# KC_BaseBoardSch.net
KiCad netlist of a schematic drawn in Altium Designer
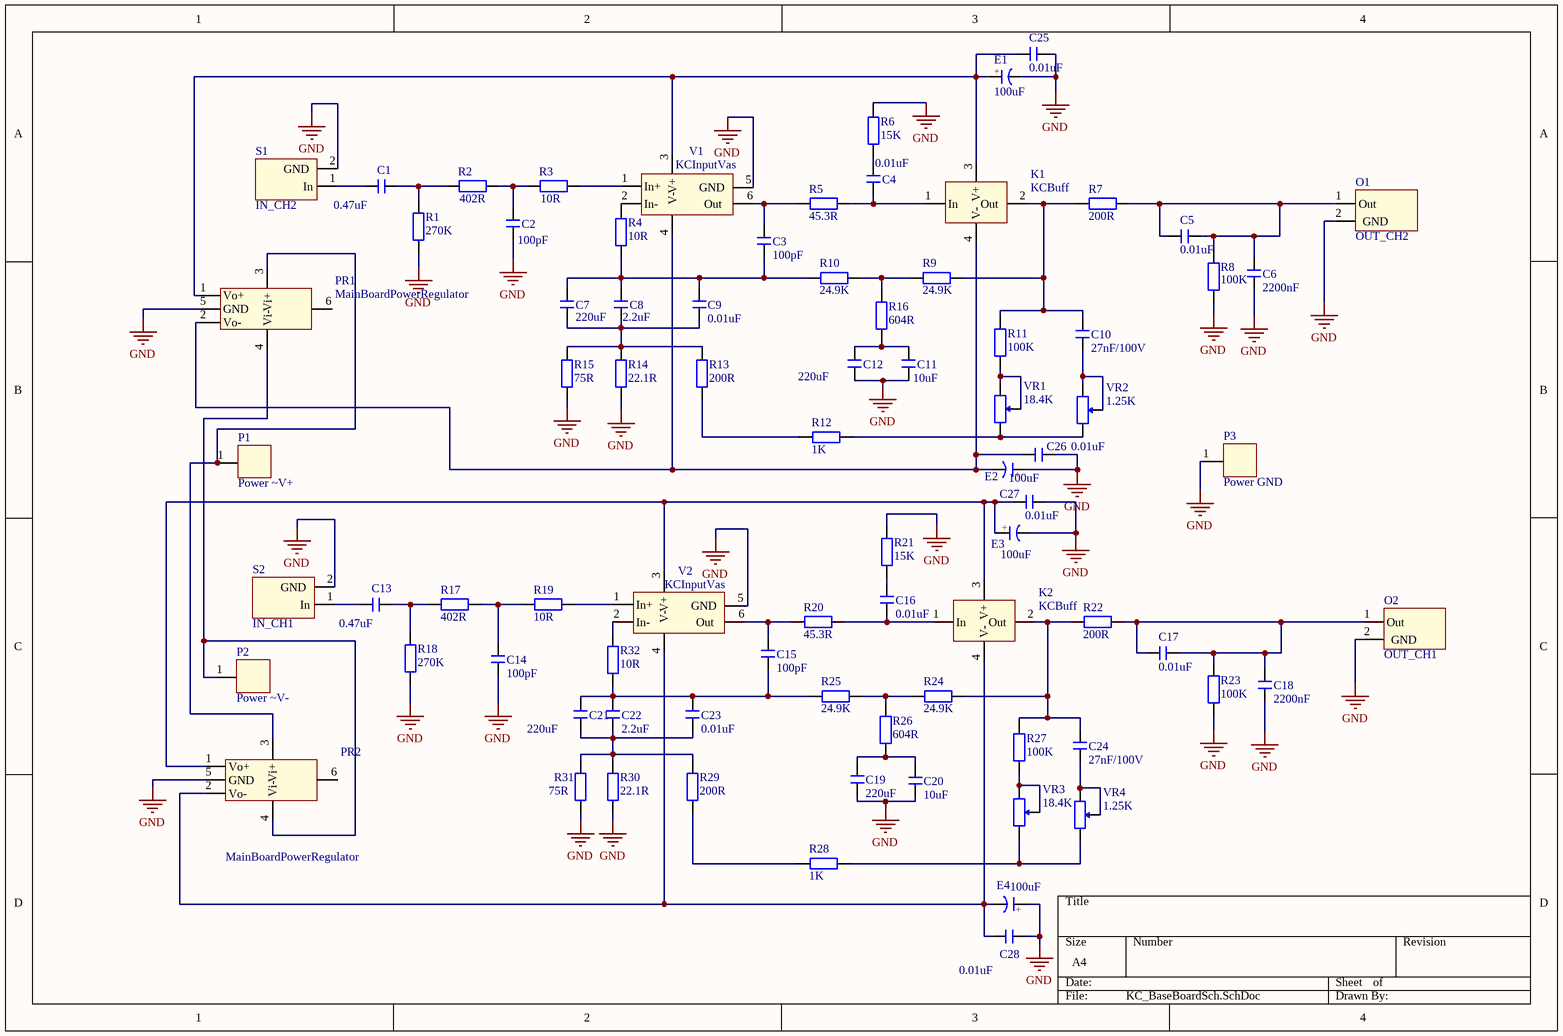
[diagram p0: KC_BaseBoardSch.SchDoc]

(export (version "E")
  (design (tool "Eeschema 10.0.6"))
  (components
    (comp (ref "C1")
      (value "0.47uF")
      (footprint "CBB 50*30*30")
      (description "CBB电容")
      (fields (field (name "版权归属") "源创客"))
      (libsource (lib "电阻-电容-电感") (part "C-CBB"))
    )
    (comp (ref "C2")
      (value "100pF")
      (footprint "CBB 6.3*6.3*5")
      (description "CBB电容")
      (fields (field (name "版权归属") "源创客"))
      (libsource (lib "电阻-电容-电感") (part "C-CBB"))
    )
    (comp (ref "C3")
      (value "100pF")
      (footprint "CBB 6.3*6.3*5")
      (description "CBB电容")
      (fields (field (name "版权归属") "源创客"))
      (libsource (lib "电阻-电容-电感") (part "C-CBB"))
    )
    (comp (ref "C4")
      (value "0.01uF")
      (footprint "CBB 6.3*6.3*5")
      (description "CBB电容")
      (fields (field (name "版权归属") "源创客"))
      (libsource (lib "电阻-电容-电感") (part "C-CBB"))
    )
    (comp (ref "C5")
      (value "0.01uF")
      (footprint "CBB 6.3*6.3*5")
      (description "CBB电容")
      (fields (field (name "版权归属") "源创客"))
      (libsource (lib "电阻-电容-电感") (part "C-CBB"))
    )
    (comp (ref "C6")
      (value "2200nF")
      (footprint "CBB 6.3*6.3*5")
      (description "CBB电容")
      (fields (field (name "版权归属") "源创客"))
      (libsource (lib "电阻-电容-电感") (part "C-CBB"))
    )
    (comp (ref "C7")
      (value "220uF")
      (footprint "CBB 6.3*6.3*5")
      (description "CBB电容")
      (fields (field (name "版权归属") "源创客"))
      (libsource (lib "电阻-电容-电感") (part "C-CBB"))
    )
    (comp (ref "C8")
      (value "2.2uF")
      (footprint "CBB 6.3*6.3*5")
      (description "CBB电容")
      (fields (field (name "版权归属") "源创客"))
      (libsource (lib "电阻-电容-电感") (part "C-CBB"))
    )
    (comp (ref "C9")
      (value "0.01uF")
      (footprint "CBB 6.3*6.3*5")
      (description "CBB电容")
      (fields (field (name "版权归属") "源创客"))
      (libsource (lib "电阻-电容-电感") (part "C-CBB"))
    )
    (comp (ref "C10")
      (value "27nF/100V")
      (footprint "CBB 15*18*11")
      (description "CBB电容")
      (fields (field (name "版权归属") "源创客"))
      (libsource (lib "电阻-电容-电感") (part "C-CBB"))
    )
    (comp (ref "C11")
      (value "10uF")
      (footprint "CBB 6.3*6.3*5")
      (description "CBB电容")
      (fields (field (name "版权归属") "源创客"))
      (libsource (lib "电阻-电容-电感") (part "C-CBB"))
    )
    (comp (ref "C12")
      (value "220uF")
      (footprint "CBB 6.3*6.3*5")
      (description "CBB电容")
      (fields (field (name "版权归属") "源创客"))
      (libsource (lib "电阻-电容-电感") (part "C-CBB"))
    )
    (comp (ref "C13")
      (value "0.47uF")
      (footprint "CBB 50*30*30")
      (description "CBB电容")
      (fields (field (name "版权归属") "源创客"))
      (libsource (lib "电阻-电容-电感") (part "C-CBB"))
    )
    (comp (ref "C14")
      (value "100pF")
      (footprint "CBB 6.3*6.3*5")
      (description "CBB电容")
      (fields (field (name "版权归属") "源创客"))
      (libsource (lib "电阻-电容-电感") (part "C-CBB"))
    )
    (comp (ref "C15")
      (value "100pF")
      (footprint "CBB 6.3*6.3*5")
      (description "CBB电容")
      (fields (field (name "版权归属") "源创客"))
      (libsource (lib "电阻-电容-电感") (part "C-CBB"))
    )
    (comp (ref "C16")
      (value "0.01uF")
      (footprint "CBB 6.3*6.3*5")
      (description "CBB电容")
      (fields (field (name "版权归属") "源创客"))
      (libsource (lib "电阻-电容-电感") (part "C-CBB"))
    )
    (comp (ref "C17")
      (value "0.01uF")
      (footprint "CBB 6.3*6.3*5")
      (description "CBB电容")
      (fields (field (name "版权归属") "源创客"))
      (libsource (lib "电阻-电容-电感") (part "C-CBB"))
    )
    (comp (ref "C18")
      (value "2200nF")
      (footprint "CBB 6.3*6.3*5")
      (description "CBB电容")
      (fields (field (name "版权归属") "源创客"))
      (libsource (lib "电阻-电容-电感") (part "C-CBB"))
    )
    (comp (ref "C19")
      (value "220uF")
      (footprint "CBB 6.3*6.3*5")
      (description "CBB电容")
      (fields (field (name "版权归属") "源创客"))
      (libsource (lib "电阻-电容-电感") (part "C-CBB"))
    )
    (comp (ref "C20")
      (value "10uF")
      (footprint "CBB 6.3*6.3*5")
      (description "CBB电容")
      (fields (field (name "版权归属") "源创客"))
      (libsource (lib "电阻-电容-电感") (part "C-CBB"))
    )
    (comp (ref "C21")
      (value "220uF")
      (footprint "CBB 6.3*6.3*5")
      (description "CBB电容")
      (fields (field (name "版权归属") "源创客"))
      (libsource (lib "电阻-电容-电感") (part "C-CBB"))
    )
    (comp (ref "C22")
      (value "2.2uF")
      (footprint "CBB 6.3*6.3*5")
      (description "CBB电容")
      (fields (field (name "版权归属") "源创客"))
      (libsource (lib "电阻-电容-电感") (part "C-CBB"))
    )
    (comp (ref "C23")
      (value "0.01uF")
      (footprint "CBB 6.3*6.3*5")
      (description "CBB电容")
      (fields (field (name "版权归属") "源创客"))
      (libsource (lib "电阻-电容-电感") (part "C-CBB"))
    )
    (comp (ref "C24")
      (value "27nF/100V")
      (footprint "CBB 15*18*11")
      (description "CBB电容")
      (fields (field (name "版权归属") "源创客"))
      (libsource (lib "电阻-电容-电感") (part "C-CBB"))
    )
    (comp (ref "C25")
      (value "0.01uF")
      (footprint "CBB 6.3*6.3*5")
      (description "CBB电容")
      (fields (field (name "版权归属") "源创客"))
      (libsource (lib "电阻-电容-电感") (part "C-CBB"))
    )
    (comp (ref "C26")
      (value "0.01uF")
      (footprint "CBB 6.3*6.3*5")
      (description "CBB电容")
      (fields (field (name "版权归属") "源创客"))
      (libsource (lib "电阻-电容-电感") (part "C-CBB"))
    )
    (comp (ref "C27")
      (value "0.01uF")
      (footprint "CBB 6.3*6.3*5")
      (description "CBB电容")
      (fields (field (name "版权归属") "源创客"))
      (libsource (lib "电阻-电容-电感") (part "C-CBB"))
    )
    (comp (ref "C28")
      (value "0.01uF")
      (footprint "CBB 6.3*6.3*5")
      (description "CBB电容")
      (fields (field (name "版权归属") "源创客"))
      (libsource (lib "电阻-电容-电感") (part "C-CBB"))
    )
    (comp (ref "E1")
      (value "100uF")
      (footprint "CAP 5.0*10*20")
      (description "直插电解电容")
      (fields (field (name "版权归属") "源创客"))
      (libsource (lib "电阻-电容-电感") (part "C-CAP"))
    )
    (comp (ref "E2")
      (value "100uF")
      (footprint "CAP 5.0*10*20")
      (description "直插电解电容")
      (fields (field (name "版权归属") "源创客"))
      (libsource (lib "电阻-电容-电感") (part "C-CAP"))
    )
    (comp (ref "E3")
      (value "100uF")
      (footprint "CAP 5.0*10*20")
      (description "直插电解电容")
      (fields (field (name "版权归属") "源创客"))
      (libsource (lib "电阻-电容-电感") (part "C-CAP"))
    )
    (comp (ref "E4")
      (value "100uF")
      (footprint "CAP 5.0*10*20")
      (description "直插电解电容")
      (fields (field (name "版权归属") "源创客"))
      (libsource (lib "电阻-电容-电感") (part "C-CAP"))
    )
    (comp (ref "K1")
      (value "KCBuff")
      (footprint "KCBuff")
      (description "King Cello Buffer Stage")
      (libsource (lib "KC_amp") (part "KCBuff"))
    )
    (comp (ref "K2")
      (value "KCBuff")
      (footprint "KCBuff")
      (description "King Cello Buffer Stage")
      (libsource (lib "KC_amp") (part "KCBuff"))
    )
    (comp (ref "O1")
      (value "OUT_CH2")
      (footprint "Signal_Terminal")
      (description "Signal Out")
      (libsource (lib "KC_amp") (part "Signal_Out"))
    )
    (comp (ref "O2")
      (value "OUT_CH1")
      (footprint "Signal_Terminal")
      (description "Signal Out")
      (libsource (lib "KC_amp") (part "Signal_Out"))
    )
    (comp (ref "P1")
      (value "Power ~V+")
      (footprint "SinglePin")
      (description "Power Pin")
      (libsource (lib "KC_amp") (part "PowerPin"))
    )
    (comp (ref "P2")
      (value "Power ~V-")
      (footprint "SinglePin")
      (description "Power Pin")
      (libsource (lib "KC_amp") (part "PowerPin"))
    )
    (comp (ref "P3") (value "Power GND") (footprint "SinglePin") (libsource (lib "KC_amp") (part "PowerPin")))
    (comp (ref "PR1")
      (value "MainBoardPowerRegulator")
      (footprint "KC_MBPowerReg")
      (description "King Cello Main Board Power Regulator")
      (libsource (lib "KC_amp") (part "MainBoardPowerRegulator"))
    )
    (comp (ref "PR2")
      (value "MainBoardPowerRegulator")
      (footprint "KC_MBPowerReg")
      (description "King Cello Main Board Power Regulator")
      (libsource (lib "KC_amp") (part "MainBoardPowerRegulator"))
    )
    (comp (ref "R1")
      (value "270K")
      (footprint "RS 1/2W")
      (description "直插色环电阻")
      (fields (field (name "版权归属") "源创客"))
      (libsource (lib "电阻-电容-电感") (part "R-CRR"))
    )
    (comp (ref "R2")
      (value "402R")
      (footprint "RS 1/2W")
      (description "直插色环电阻")
      (fields (field (name "版权归属") "源创客"))
      (libsource (lib "电阻-电容-电感") (part "R-CRR"))
    )
    (comp (ref "R3")
      (value "10R")
      (footprint "RS 1/2W")
      (description "直插色环电阻")
      (fields (field (name "版权归属") "源创客"))
      (libsource (lib "电阻-电容-电感") (part "R-CRR"))
    )
    (comp (ref "R4")
      (value "10R")
      (footprint "RS 1/2W")
      (description "直插色环电阻")
      (fields (field (name "版权归属") "源创客"))
      (libsource (lib "电阻-电容-电感") (part "R-CRR"))
    )
    (comp (ref "R5")
      (value "45.3R")
      (footprint "RS 1/2W")
      (description "直插色环电阻")
      (fields (field (name "版权归属") "源创客"))
      (libsource (lib "电阻-电容-电感") (part "R-CRR"))
    )
    (comp (ref "R6")
      (value "15K")
      (footprint "RS 1/2W")
      (description "直插色环电阻")
      (fields (field (name "版权归属") "源创客"))
      (libsource (lib "电阻-电容-电感") (part "R-CRR"))
    )
    (comp (ref "R7")
      (value "200R")
      (footprint "RS 1W")
      (description "直插色环电阻")
      (fields (field (name "版权归属") "源创客"))
      (libsource (lib "电阻-电容-电感") (part "R-CRR"))
    )
    (comp (ref "R8")
      (value "100K")
      (footprint "RS 1/2W")
      (description "直插色环电阻")
      (fields (field (name "版权归属") "源创客"))
      (libsource (lib "电阻-电容-电感") (part "R-CRR"))
    )
    (comp (ref "R9")
      (value "24.9K")
      (footprint "RS 1/2W")
      (description "直插色环电阻")
      (fields (field (name "版权归属") "源创客"))
      (libsource (lib "电阻-电容-电感") (part "R-CRR"))
    )
    (comp (ref "R10")
      (value "24.9K")
      (footprint "RS 1/2W")
      (description "直插色环电阻")
      (fields (field (name "版权归属") "源创客"))
      (libsource (lib "电阻-电容-电感") (part "R-CRR"))
    )
    (comp (ref "R11")
      (value "100K")
      (footprint "RS 1/2W")
      (description "直插色环电阻")
      (fields (field (name "版权归属") "源创客"))
      (libsource (lib "电阻-电容-电感") (part "R-CRR"))
    )
    (comp (ref "R12")
      (value "1K")
      (footprint "RS 1/2W")
      (description "直插色环电阻")
      (fields (field (name "版权归属") "源创客"))
      (libsource (lib "电阻-电容-电感") (part "R-CRR"))
    )
    (comp (ref "R13")
      (value "200R")
      (footprint "RS 1/2W")
      (description "直插色环电阻")
      (fields (field (name "版权归属") "源创客"))
      (libsource (lib "电阻-电容-电感") (part "R-CRR"))
    )
    (comp (ref "R14")
      (value "22.1R")
      (footprint "RS 1/2W")
      (description "直插色环电阻")
      (fields (field (name "版权归属") "源创客"))
      (libsource (lib "电阻-电容-电感") (part "R-CRR"))
    )
    (comp (ref "R15")
      (value "75R")
      (footprint "RS 1/2W")
      (description "直插色环电阻")
      (fields (field (name "版权归属") "源创客"))
      (libsource (lib "电阻-电容-电感") (part "R-CRR"))
    )
    (comp (ref "R16")
      (value "604R")
      (footprint "RS 1W")
      (description "直插色环电阻")
      (fields (field (name "版权归属") "源创客"))
      (libsource (lib "电阻-电容-电感") (part "R-CRR"))
    )
    (comp (ref "R17")
      (value "402R")
      (footprint "RS 1/2W")
      (description "直插色环电阻")
      (fields (field (name "版权归属") "源创客"))
      (libsource (lib "电阻-电容-电感") (part "R-CRR"))
    )
    (comp (ref "R18")
      (value "270K")
      (footprint "RS 1/2W")
      (description "直插色环电阻")
      (fields (field (name "版权归属") "源创客"))
      (libsource (lib "电阻-电容-电感") (part "R-CRR"))
    )
    (comp (ref "R19")
      (value "10R")
      (footprint "RS 1/2W")
      (description "直插色环电阻")
      (fields (field (name "版权归属") "源创客"))
      (libsource (lib "电阻-电容-电感") (part "R-CRR"))
    )
    (comp (ref "R20")
      (value "45.3R")
      (footprint "RS 1/2W")
      (description "直插色环电阻")
      (fields (field (name "版权归属") "源创客"))
      (libsource (lib "电阻-电容-电感") (part "R-CRR"))
    )
    (comp (ref "R21")
      (value "15K")
      (footprint "RS 1/2W")
      (description "直插色环电阻")
      (fields (field (name "版权归属") "源创客"))
      (libsource (lib "电阻-电容-电感") (part "R-CRR"))
    )
    (comp (ref "R22")
      (value "200R")
      (footprint "RS 1W")
      (description "直插色环电阻")
      (fields (field (name "版权归属") "源创客"))
      (libsource (lib "电阻-电容-电感") (part "R-CRR"))
    )
    (comp (ref "R23")
      (value "100K")
      (footprint "RS 1/2W")
      (description "直插色环电阻")
      (fields (field (name "版权归属") "源创客"))
      (libsource (lib "电阻-电容-电感") (part "R-CRR"))
    )
    (comp (ref "R24")
      (value "24.9K")
      (footprint "RS 1/2W")
      (description "直插色环电阻")
      (fields (field (name "版权归属") "源创客"))
      (libsource (lib "电阻-电容-电感") (part "R-CRR"))
    )
    (comp (ref "R25")
      (value "24.9K")
      (footprint "RS 1/2W")
      (description "直插色环电阻")
      (fields (field (name "版权归属") "源创客"))
      (libsource (lib "电阻-电容-电感") (part "R-CRR"))
    )
    (comp (ref "R26")
      (value "604R")
      (footprint "RS 1W")
      (description "直插色环电阻")
      (fields (field (name "版权归属") "源创客"))
      (libsource (lib "电阻-电容-电感") (part "R-CRR"))
    )
    (comp (ref "R27")
      (value "100K")
      (footprint "RS 1/2W")
      (description "直插色环电阻")
      (fields (field (name "版权归属") "源创客"))
      (libsource (lib "电阻-电容-电感") (part "R-CRR"))
    )
    (comp (ref "R28")
      (value "1K")
      (footprint "RS 1/2W")
      (description "直插色环电阻")
      (fields (field (name "版权归属") "源创客"))
      (libsource (lib "电阻-电容-电感") (part "R-CRR"))
    )
    (comp (ref "R29")
      (value "200R")
      (footprint "RS 1/2W")
      (description "直插色环电阻")
      (fields (field (name "版权归属") "源创客"))
      (libsource (lib "电阻-电容-电感") (part "R-CRR"))
    )
    (comp (ref "R30")
      (value "22.1R")
      (footprint "RS 1/2W")
      (description "直插色环电阻")
      (fields (field (name "版权归属") "源创客"))
      (libsource (lib "电阻-电容-电感") (part "R-CRR"))
    )
    (comp (ref "R31")
      (value "75R")
      (footprint "RS 1/2W")
      (description "直插色环电阻")
      (fields (field (name "版权归属") "源创客"))
      (libsource (lib "电阻-电容-电感") (part "R-CRR"))
    )
    (comp (ref "R32")
      (value "10R")
      (footprint "RS 1/2W")
      (description "直插色环电阻")
      (fields (field (name "版权归属") "源创客"))
      (libsource (lib "电阻-电容-电感") (part "R-CRR"))
    )
    (comp (ref "S1")
      (value "IN_CH2")
      (footprint "Signal_Terminal")
      (description "Signal In")
      (libsource (lib "KC_amp") (part "Signal_In"))
    )
    (comp (ref "S2")
      (value "IN_CH1")
      (footprint "Signal_Terminal")
      (description "Signal In")
      (libsource (lib "KC_amp") (part "Signal_In"))
    )
    (comp (ref "V1")
      (value "KCInputVas")
      (footprint "KCIn_VAS")
      (description "King Cello Input Stage and VAS")
      (libsource (lib "KC_amp") (part "KCInputVas"))
    )
    (comp (ref "V2")
      (value "KCInputVas")
      (footprint "KCIn_VAS")
      (description "King Cello Input Stage and VAS")
      (libsource (lib "KC_amp") (part "KCInputVas"))
    )
    (comp (ref "VR1")
      (value "18.4K")
      (footprint "RS 1/2W-VR")
      (description "直插可调电阻-顶调")
      (libsource (lib "电阻-电容-电感") (part "VR-W"))
    )
    (comp (ref "VR2")
      (value "1.25K")
      (footprint "RS 1/2W-VR")
      (description "直插可调电阻-顶调")
      (libsource (lib "电阻-电容-电感") (part "VR-W"))
    )
    (comp (ref "VR3")
      (value "18.4K")
      (footprint "RS 1/2W-VR")
      (description "直插可调电阻-顶调")
      (libsource (lib "电阻-电容-电感") (part "VR-W"))
    )
    (comp (ref "VR4")
      (value "1.25K")
      (footprint "RS 1/2W-VR")
      (description "直插可调电阻-顶调")
      (libsource (lib "电阻-电容-电感") (part "VR-W"))
    )
  )
  (nets
    (net (code "1") (name "GND") (class "Default")
      (node (ref "C11") (pin "1") (pinfunction "1_1") (pintype "passive"))
      (node (ref "C12") (pin "1") (pinfunction "1_1") (pintype "passive"))
      (node (ref "C14") (pin "1") (pinfunction "1_1") (pintype "passive"))
      (node (ref "C18") (pin "2") (pinfunction "2_2") (pintype "passive"))
      (node (ref "C19") (pin "2") (pinfunction "2_2") (pintype "passive"))
      (node (ref "C2") (pin "1") (pinfunction "1_1") (pintype "passive"))
      (node (ref "C20") (pin "2") (pinfunction "2_2") (pintype "passive"))
      (node (ref "C25") (pin "2") (pinfunction "2_2") (pintype "passive"))
      (node (ref "C26") (pin "2") (pinfunction "2_2") (pintype "passive"))
      (node (ref "C27") (pin "2") (pinfunction "2_2") (pintype "passive"))
      (node (ref "C28") (pin "2") (pinfunction "2_2") (pintype "passive"))
      (node (ref "C6") (pin "1") (pinfunction "1_1") (pintype "passive"))
      (node (ref "E1") (pin "2") (pinfunction "K_2") (pintype "passive"))
      (node (ref "E2") (pin "1") (pinfunction "A_1") (pintype "passive"))
      (node (ref "E3") (pin "2") (pinfunction "K_2") (pintype "passive"))
      (node (ref "E4") (pin "1") (pinfunction "A_1") (pintype "passive"))
      (node (ref "O1") (pin "2") (pinfunction "GND_2") (pintype "passive"))
      (node (ref "O2") (pin "2") (pinfunction "GND_2") (pintype "passive"))
      (node (ref "P3") (pin "1") (pintype "passive"))
      (node (ref "PR1") (pin "5") (pinfunction "GND_5") (pintype "passive"))
      (node (ref "PR2") (pin "5") (pinfunction "GND_5") (pintype "passive"))
      (node (ref "R1") (pin "1") (pinfunction "1_1") (pintype "passive"))
      (node (ref "R14") (pin "1") (pinfunction "1_1") (pintype "passive"))
      (node (ref "R15") (pin "1") (pinfunction "1_1") (pintype "passive"))
      (node (ref "R18") (pin "1") (pinfunction "1_1") (pintype "passive"))
      (node (ref "R21") (pin "2") (pinfunction "2_2") (pintype "passive"))
      (node (ref "R23") (pin "2") (pinfunction "2_2") (pintype "passive"))
      (node (ref "R30") (pin "1") (pinfunction "1_1") (pintype "passive"))
      (node (ref "R31") (pin "1") (pinfunction "1_1") (pintype "passive"))
      (node (ref "R6") (pin "1") (pinfunction "1_1") (pintype "passive"))
      (node (ref "R8") (pin "1") (pinfunction "1_1") (pintype "passive"))
      (node (ref "S1") (pin "2") (pinfunction "GND_2") (pintype "passive"))
      (node (ref "S2") (pin "2") (pinfunction "GND_2") (pintype "passive"))
      (node (ref "V1") (pin "5") (pinfunction "GND_5") (pintype "passive"))
      (node (ref "V2") (pin "5") (pinfunction "GND_5") (pintype "passive"))
    )
    (net (code "2") (name "Net-(C1-Pad2)") (class "Default")
      (node (ref "C1") (pin "2") (pinfunction "2_2") (pintype "passive"))
      (node (ref "R1") (pin "2") (pinfunction "2_2") (pintype "passive"))
      (node (ref "R2") (pin "1") (pinfunction "1_1") (pintype "passive"))
    )
    (net (code "3") (name "Net-(C2-Pad2)") (class "Default")
      (node (ref "C2") (pin "2") (pinfunction "2_2") (pintype "passive"))
      (node (ref "R2") (pin "2") (pinfunction "2_2") (pintype "passive"))
      (node (ref "R3") (pin "2") (pinfunction "2_2") (pintype "passive"))
    )
    (net (code "4") (name "Net-(C3-Pad1)") (class "Default")
      (node (ref "C3") (pin "1") (pinfunction "1_1") (pintype "passive"))
      (node (ref "C7") (pin "2") (pinfunction "2_2") (pintype "passive"))
      (node (ref "C8") (pin "2") (pinfunction "2_2") (pintype "passive"))
      (node (ref "C9") (pin "2") (pinfunction "2_2") (pintype "passive"))
      (node (ref "R10") (pin "2") (pinfunction "2_2") (pintype "passive"))
      (node (ref "R4") (pin "1") (pinfunction "1_1") (pintype "passive"))
    )
    (net (code "5") (name "Net-(C4-Pad2)") (class "Default")
      (node (ref "C4") (pin "2") (pinfunction "2_2") (pintype "passive"))
      (node (ref "R6") (pin "2") (pinfunction "2_2") (pintype "passive"))
    )
    (net (code "6") (name "Net-(C7-Pad1)") (class "Default")
      (node (ref "C7") (pin "1") (pinfunction "1_1") (pintype "passive"))
      (node (ref "C8") (pin "1") (pinfunction "1_1") (pintype "passive"))
      (node (ref "C9") (pin "1") (pinfunction "1_1") (pintype "passive"))
      (node (ref "R13") (pin "2") (pinfunction "2_2") (pintype "passive"))
      (node (ref "R14") (pin "2") (pinfunction "2_2") (pintype "passive"))
      (node (ref "R15") (pin "2") (pinfunction "2_2") (pintype "passive"))
    )
    (net (code "7") (name "Net-(C10-Pad1)") (class "Default")
      (node (ref "C10") (pin "1") (pinfunction "1_1") (pintype "passive"))
      (node (ref "VR2") (pin "1") (pinfunction "1_1") (pintype "passive"))
      (node (ref "VR2") (pin "3") (pinfunction "3_3") (pintype "passive"))
    )
    (net (code "8") (name "Net-(C11-Pad2)") (class "Default")
      (node (ref "C11") (pin "2") (pinfunction "2_2") (pintype "passive"))
      (node (ref "C12") (pin "2") (pinfunction "2_2") (pintype "passive"))
      (node (ref "R16") (pin "1") (pinfunction "1_1") (pintype "passive"))
    )
    (net (code "9") (name "Net-(C13-Pad2)") (class "Default")
      (node (ref "C13") (pin "2") (pinfunction "2_2") (pintype "passive"))
      (node (ref "R17") (pin "1") (pinfunction "1_1") (pintype "passive"))
      (node (ref "R18") (pin "2") (pinfunction "2_2") (pintype "passive"))
    )
    (net (code "10") (name "Net-(C14-Pad2)") (class "Default")
      (node (ref "C14") (pin "2") (pinfunction "2_2") (pintype "passive"))
      (node (ref "R17") (pin "2") (pinfunction "2_2") (pintype "passive"))
      (node (ref "R19") (pin "1") (pinfunction "1_1") (pintype "passive"))
    )
    (net (code "11") (name "Net-(C15-Pad1)") (class "Default")
      (node (ref "C15") (pin "1") (pinfunction "1_1") (pintype "passive"))
      (node (ref "C21") (pin "1") (pinfunction "1_1") (pintype "passive"))
      (node (ref "C22") (pin "1") (pinfunction "1_1") (pintype "passive"))
      (node (ref "C23") (pin "1") (pinfunction "1_1") (pintype "passive"))
      (node (ref "R25") (pin "1") (pinfunction "1_1") (pintype "passive"))
      (node (ref "R32") (pin "1") (pinfunction "1_1") (pintype "passive"))
    )
    (net (code "12") (name "Net-(C16-Pad2)") (class "Default")
      (node (ref "C16") (pin "2") (pinfunction "2_2") (pintype "passive"))
      (node (ref "R21") (pin "1") (pinfunction "1_1") (pintype "passive"))
    )
    (net (code "13") (name "Net-(C19-Pad1)") (class "Default")
      (node (ref "C19") (pin "1") (pinfunction "1_1") (pintype "passive"))
      (node (ref "C20") (pin "1") (pinfunction "1_1") (pintype "passive"))
      (node (ref "R26") (pin "1") (pinfunction "1_1") (pintype "passive"))
    )
    (net (code "14") (name "Net-(C21-Pad2)") (class "Default")
      (node (ref "C21") (pin "2") (pinfunction "2_2") (pintype "passive"))
      (node (ref "C22") (pin "2") (pinfunction "2_2") (pintype "passive"))
      (node (ref "C23") (pin "2") (pinfunction "2_2") (pintype "passive"))
      (node (ref "R29") (pin "2") (pinfunction "2_2") (pintype "passive"))
      (node (ref "R30") (pin "2") (pinfunction "2_2") (pintype "passive"))
      (node (ref "R31") (pin "2") (pinfunction "2_2") (pintype "passive"))
    )
    (net (code "15") (name "Net-(C24-Pad2)") (class "Default")
      (node (ref "C24") (pin "2") (pinfunction "2_2") (pintype "passive"))
      (node (ref "VR4") (pin "1") (pinfunction "1_1") (pintype "passive"))
      (node (ref "VR4") (pin "3") (pinfunction "3_3") (pintype "passive"))
    )
    (net (code "16") (name "Net-(E1-A)") (class "Default")
      (node (ref "C25") (pin "1") (pinfunction "1_1") (pintype "passive"))
      (node (ref "E1") (pin "1") (pinfunction "A_1") (pintype "passive"))
      (node (ref "K1") (pin "3") (pinfunction "V+_3") (pintype "passive"))
      (node (ref "PR1") (pin "1") (pinfunction "Vo+_1") (pintype "passive"))
      (node (ref "V1") (pin "3") (pinfunction "V+_3") (pintype "passive"))
    )
    (net (code "17") (name "Net-(E2-K)") (class "Default")
      (node (ref "C26") (pin "1") (pinfunction "1_1") (pintype "passive"))
      (node (ref "E2") (pin "2") (pinfunction "K_2") (pintype "passive"))
      (node (ref "K1") (pin "4") (pinfunction "V-_4") (pintype "passive"))
      (node (ref "PR1") (pin "2") (pinfunction "Vo-_2") (pintype "passive"))
      (node (ref "V1") (pin "4") (pinfunction "V-_4") (pintype "passive"))
    )
    (net (code "18") (name "Net-(E3-A)") (class "Default")
      (node (ref "C27") (pin "1") (pinfunction "1_1") (pintype "passive"))
      (node (ref "E3") (pin "1") (pinfunction "A_1") (pintype "passive"))
      (node (ref "K2") (pin "3") (pinfunction "V+_3") (pintype "passive"))
      (node (ref "PR2") (pin "1") (pinfunction "Vo+_1") (pintype "passive"))
      (node (ref "V2") (pin "3") (pinfunction "V+_3") (pintype "passive"))
    )
    (net (code "19") (name "Net-(E4-K)") (class "Default")
      (node (ref "C28") (pin "1") (pinfunction "1_1") (pintype "passive"))
      (node (ref "E4") (pin "2") (pinfunction "K_2") (pintype "passive"))
      (node (ref "K2") (pin "4") (pinfunction "V-_4") (pintype "passive"))
      (node (ref "PR2") (pin "2") (pinfunction "Vo-_2") (pintype "passive"))
      (node (ref "V2") (pin "4") (pinfunction "V-_4") (pintype "passive"))
    )
    (net (code "20") (name "Net-(K1-In)") (class "Default")
      (node (ref "C4") (pin "1") (pinfunction "1_1") (pintype "passive"))
      (node (ref "K1") (pin "1") (pinfunction "In_1") (pintype "passive"))
      (node (ref "R5") (pin "1") (pinfunction "1_1") (pintype "passive"))
    )
    (net (code "21") (name "Net-(K1-Out)") (class "Default")
      (node (ref "C10") (pin "2") (pinfunction "2_2") (pintype "passive"))
      (node (ref "K1") (pin "2") (pinfunction "Out_2") (pintype "passive"))
      (node (ref "R11") (pin "1") (pinfunction "1_1") (pintype "passive"))
      (node (ref "R7") (pin "1") (pinfunction "1_1") (pintype "passive"))
      (node (ref "R9") (pin "1") (pinfunction "1_1") (pintype "passive"))
    )
    (net (code "22") (name "Net-(K2-In)") (class "Default")
      (node (ref "C16") (pin "1") (pinfunction "1_1") (pintype "passive"))
      (node (ref "K2") (pin "1") (pinfunction "In_1") (pintype "passive"))
      (node (ref "R20") (pin "2") (pinfunction "2_2") (pintype "passive"))
    )
    (net (code "23") (name "Net-(K2-Out)") (class "Default")
      (node (ref "C24") (pin "1") (pinfunction "1_1") (pintype "passive"))
      (node (ref "K2") (pin "2") (pinfunction "Out_2") (pintype "passive"))
      (node (ref "R22") (pin "2") (pinfunction "2_2") (pintype "passive"))
      (node (ref "R24") (pin "2") (pinfunction "2_2") (pintype "passive"))
      (node (ref "R27") (pin "1") (pinfunction "1_1") (pintype "passive"))
    )
    (net (code "24") (name "Net-(O1-Out)") (class "Default")
      (node (ref "C5") (pin "1") (pinfunction "1_1") (pintype "passive"))
      (node (ref "C5") (pin "2") (pinfunction "2_2") (pintype "passive"))
      (node (ref "C6") (pin "2") (pinfunction "2_2") (pintype "passive"))
      (node (ref "O1") (pin "1") (pinfunction "Out_1") (pintype "passive"))
      (node (ref "R7") (pin "2") (pinfunction "2_2") (pintype "passive"))
      (node (ref "R8") (pin "2") (pinfunction "2_2") (pintype "passive"))
    )
    (net (code "25") (name "Net-(O2-Out)") (class "Default")
      (node (ref "C17") (pin "1") (pinfunction "1_1") (pintype "passive"))
      (node (ref "C17") (pin "2") (pinfunction "2_2") (pintype "passive"))
      (node (ref "C18") (pin "1") (pinfunction "1_1") (pintype "passive"))
      (node (ref "O2") (pin "1") (pinfunction "Out_1") (pintype "passive"))
      (node (ref "R22") (pin "1") (pinfunction "1_1") (pintype "passive"))
      (node (ref "R23") (pin "1") (pinfunction "1_1") (pintype "passive"))
    )
    (net (code "26") (name "Net-(PR1-Vi+)") (class "Default")
      (node (ref "P1") (pin "1") (pintype "passive"))
      (node (ref "PR1") (pin "3") (pinfunction "Vi+_3") (pintype "passive"))
      (node (ref "PR2") (pin "3") (pinfunction "Vi+_3") (pintype "passive"))
    )
    (net (code "27") (name "Net-(PR1-Vi-)") (class "Default")
      (node (ref "P2") (pin "1") (pintype "passive"))
      (node (ref "PR1") (pin "4") (pinfunction "Vi-_4") (pintype "passive"))
      (node (ref "PR2") (pin "4") (pinfunction "Vi-_4") (pintype "passive"))
    )
    (net (code "28") (name "Net-(R10-Pad1)") (class "Default")
      (node (ref "R10") (pin "1") (pinfunction "1_1") (pintype "passive"))
      (node (ref "R16") (pin "2") (pinfunction "2_2") (pintype "passive"))
      (node (ref "R9") (pin "2") (pinfunction "2_2") (pintype "passive"))
    )
    (net (code "29") (name "Net-(R11-Pad2)") (class "Default")
      (node (ref "R11") (pin "2") (pinfunction "2_2") (pintype "passive"))
      (node (ref "VR1") (pin "1") (pinfunction "1_1") (pintype "passive"))
      (node (ref "VR1") (pin "3") (pinfunction "3_3") (pintype "passive"))
    )
    (net (code "30") (name "Net-(R12-Pad1)") (class "Default")
      (node (ref "R12") (pin "1") (pinfunction "1_1") (pintype "passive"))
      (node (ref "R13") (pin "1") (pinfunction "1_1") (pintype "passive"))
    )
    (net (code "31") (name "Net-(R12-Pad2)") (class "Default")
      (node (ref "R12") (pin "2") (pinfunction "2_2") (pintype "passive"))
      (node (ref "VR1") (pin "2") (pinfunction "2_2") (pintype "passive"))
      (node (ref "VR2") (pin "2") (pinfunction "2_2") (pintype "passive"))
    )
    (net (code "32") (name "Net-(R24-Pad1)") (class "Default")
      (node (ref "R24") (pin "1") (pinfunction "1_1") (pintype "passive"))
      (node (ref "R25") (pin "2") (pinfunction "2_2") (pintype "passive"))
      (node (ref "R26") (pin "2") (pinfunction "2_2") (pintype "passive"))
    )
    (net (code "33") (name "Net-(R27-Pad2)") (class "Default")
      (node (ref "R27") (pin "2") (pinfunction "2_2") (pintype "passive"))
      (node (ref "VR3") (pin "1") (pinfunction "1_1") (pintype "passive"))
      (node (ref "VR3") (pin "3") (pinfunction "3_3") (pintype "passive"))
    )
    (net (code "34") (name "Net-(R28-Pad1)") (class "Default")
      (node (ref "R28") (pin "1") (pinfunction "1_1") (pintype "passive"))
      (node (ref "R29") (pin "1") (pinfunction "1_1") (pintype "passive"))
    )
    (net (code "35") (name "Net-(R28-Pad2)") (class "Default")
      (node (ref "R28") (pin "2") (pinfunction "2_2") (pintype "passive"))
      (node (ref "VR3") (pin "2") (pinfunction "2_2") (pintype "passive"))
      (node (ref "VR4") (pin "2") (pinfunction "2_2") (pintype "passive"))
    )
    (net (code "36") (name "Net-(S1-In)") (class "Default")
      (node (ref "C1") (pin "1") (pinfunction "1_1") (pintype "passive"))
      (node (ref "S1") (pin "1") (pinfunction "In_1") (pintype "passive"))
    )
    (net (code "37") (name "Net-(S2-In)") (class "Default")
      (node (ref "C13") (pin "1") (pinfunction "1_1") (pintype "passive"))
      (node (ref "S2") (pin "1") (pinfunction "In_1") (pintype "passive"))
    )
    (net (code "38") (name "Net-(V1-In+)") (class "Default")
      (node (ref "R3") (pin "1") (pinfunction "1_1") (pintype "passive"))
      (node (ref "V1") (pin "1") (pinfunction "In+_1") (pintype "passive"))
    )
    (net (code "39") (name "Net-(V1-In-)") (class "Default")
      (node (ref "R4") (pin "2") (pinfunction "2_2") (pintype "passive"))
      (node (ref "V1") (pin "2") (pinfunction "In-_2") (pintype "passive"))
    )
    (net (code "40") (name "Net-(V1-Out)") (class "Default")
      (node (ref "C3") (pin "2") (pinfunction "2_2") (pintype "passive"))
      (node (ref "R5") (pin "2") (pinfunction "2_2") (pintype "passive"))
      (node (ref "V1") (pin "6") (pinfunction "Out_6") (pintype "passive"))
    )
    (net (code "41") (name "Net-(V2-In+)") (class "Default")
      (node (ref "R19") (pin "2") (pinfunction "2_2") (pintype "passive"))
      (node (ref "V2") (pin "1") (pinfunction "In+_1") (pintype "passive"))
    )
    (net (code "42") (name "Net-(V2-In-)") (class "Default")
      (node (ref "R32") (pin "2") (pinfunction "2_2") (pintype "passive"))
      (node (ref "V2") (pin "2") (pinfunction "In-_2") (pintype "passive"))
    )
    (net (code "43") (name "Net-(V2-Out)") (class "Default")
      (node (ref "C15") (pin "2") (pinfunction "2_2") (pintype "passive"))
      (node (ref "R20") (pin "1") (pinfunction "1_1") (pintype "passive"))
      (node (ref "V2") (pin "6") (pinfunction "Out_6") (pintype "passive"))
    )
    (net (code "44") (name "unconnected-(PR1-Pad6)") (class "Default")
      (node (ref "PR1") (pin "6") (pintype "passive"))
    )
    (net (code "45") (name "unconnected-(PR2-Pad6)") (class "Default")
      (node (ref "PR2") (pin "6") (pintype "passive"))
    )
  )
)
